# Lab10.net
KiCad netlist of a schematic drawn in Altium Designer
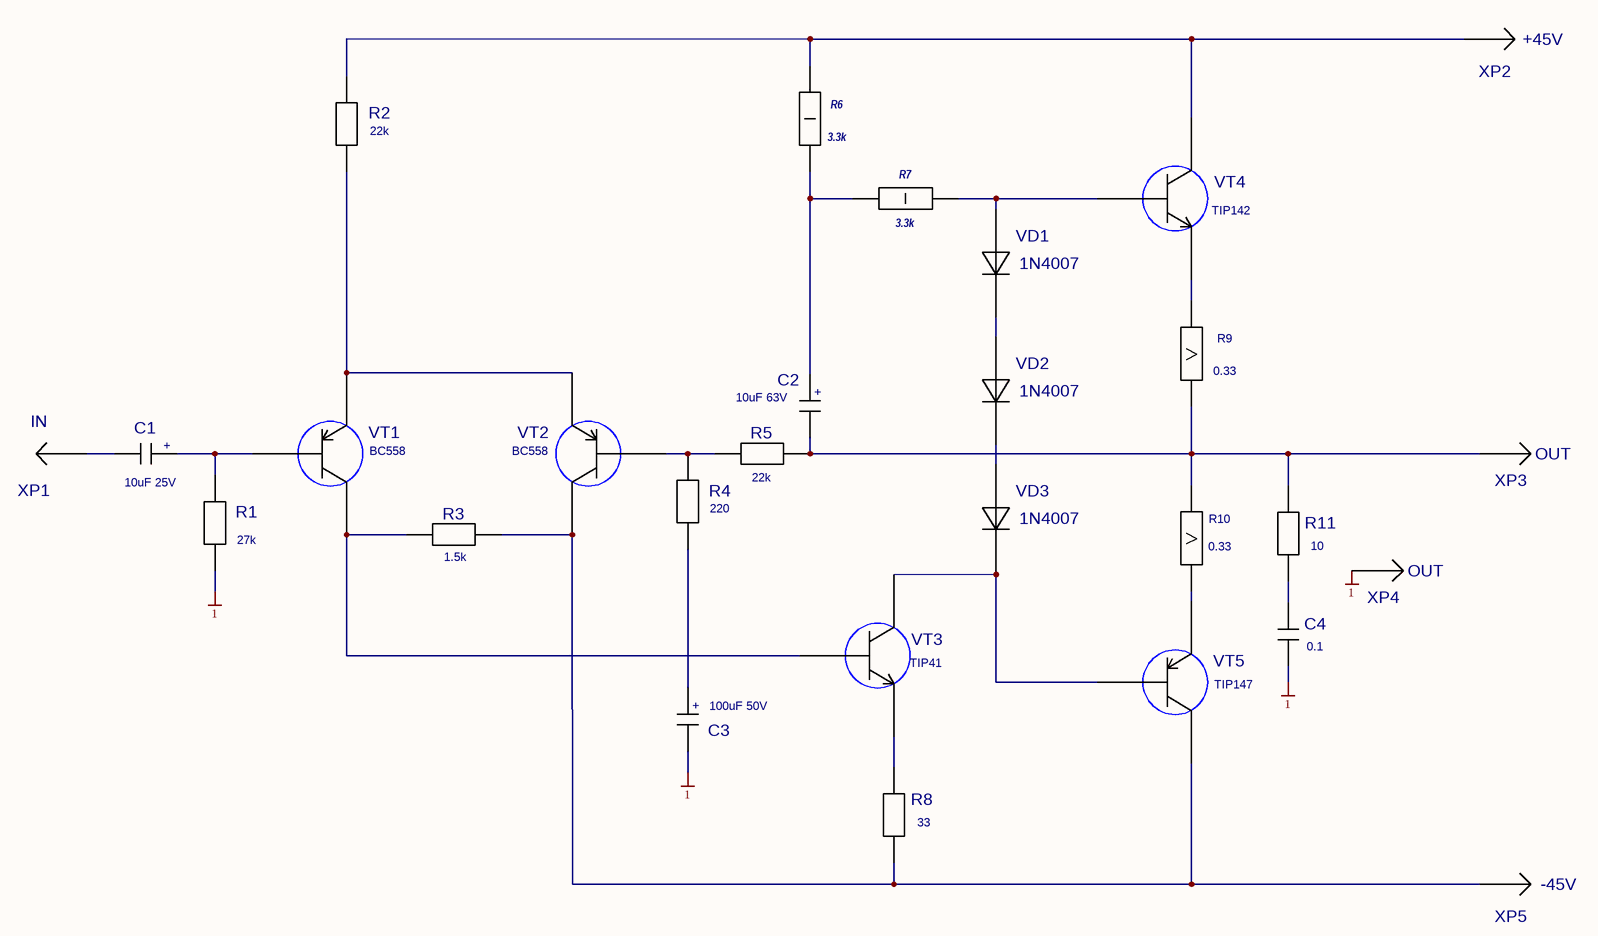
[diagram p0: Lab10.SCHDOC]

(export (version "E")
  (design (tool "Eeschema 10.0.6"))
  (components
    (comp (ref "C1")
      (value "10uF 25V")
      (footprint "CAP2")
      (description "CAP2")
      (libsource (lib "*") (part "CAP2"))
    )
    (comp (ref "C2")
      (value "10uF 63V")
      (footprint "CAP2")
      (description "CAP2")
      (libsource (lib "*") (part "CAP2"))
    )
    (comp (ref "C3")
      (value "100uF 50V")
      (footprint "CAP2")
      (description "CAP2")
      (libsource (lib "*") (part "CAP2"))
    )
    (comp (ref "C4")
      (value "0.1")
      (footprint "CAP1")
      (description "CAP1")
      (libsource (lib "*") (part "CAP1"))
    )
    (comp (ref "R1") (value "27k") (footprint "RES") (description "RES") (libsource (lib "*") (part "RES")))
    (comp (ref "R2") (value "22k") (footprint "RES") (description "RES") (libsource (lib "*") (part "RES")))
    (comp (ref "R3") (value "1.5k") (footprint "RES") (description "RES") (libsource (lib "*") (part "RES")))
    (comp (ref "R4") (value "220") (footprint "RES") (description "RES") (libsource (lib "*") (part "RES")))
    (comp (ref "R5") (value "22k") (footprint "RES") (description "RES") (libsource (lib "*") (part "RES")))
    (comp (ref "R6")
      (value "3.3k")
      (footprint "МЛТ(1)")
      (description "МЛТ(1)")
      (libsource (lib "") (part "МЛТ(1)_1"))
    )
    (comp (ref "R7")
      (value "3.3k")
      (footprint "МЛТ(1)")
      (description "МЛТ(1)")
      (libsource (lib "*") (part "МЛТ(1)"))
    )
    (comp (ref "R8") (value "33") (footprint "RES") (description "RES") (libsource (lib "*") (part "RES")))
    (comp (ref "R9")
      (value "0.33")
      (footprint "SQP5")
      (description "SQP5")
      (libsource (lib "*") (part "SQP5"))
    )
    (comp (ref "R10")
      (value "0.33")
      (footprint "SQP5")
      (description "SQP5")
      (libsource (lib "*") (part "SQP5"))
    )
    (comp (ref "R11") (value "10") (footprint "RES") (description "RES") (libsource (lib "*") (part "RES")))
    (comp (ref "VD1") (value "1N4007") (footprint "1N4007") (libsource (lib "*") (part "1N4007")))
    (comp (ref "VD2") (value "1N4007") (footprint "1N4007") (libsource (lib "*") (part "1N4007")))
    (comp (ref "VD3") (value "1N4007") (footprint "1N4007") (libsource (lib "*") (part "1N4007")))
    (comp (ref "VT1") (value "BC558") (footprint "BC558") (libsource (lib "") (part "BC558_1")))
    (comp (ref "VT2") (value "BC558") (footprint "BC558") (libsource (lib "*") (part "BC558")))
    (comp (ref "VT3") (value "TIP41") (footprint "TIP41") (libsource (lib "*") (part "TIP41")))
    (comp (ref "VT4") (value "TIP142") (footprint "TIP142") (libsource (lib "*") (part "TIP142")))
    (comp (ref "VT5") (value "TIP147") (footprint "TIP147") (libsource (lib "*") (part "TIP147")))
    (comp (ref "XP1") (value "IN") (footprint "PAD") (description "PAD") (libsource (lib "*") (part "PAD")))
    (comp (ref "XP2") (value "+45V") (footprint "PAD") (description "PAD") (libsource (lib "*") (part "PAD")))
    (comp (ref "XP3") (value "OUT") (footprint "PAD") (description "PAD") (libsource (lib "*") (part "PAD")))
    (comp (ref "XP4") (value "OUT") (footprint "PAD") (description "PAD") (libsource (lib "*") (part "PAD")))
    (comp (ref "XP5") (value "-45V") (footprint "PAD") (description "PAD") (libsource (lib "*") (part "PAD")))
  )
  (nets
    (net (code "1") (name "1") (class "Default")
      (node (ref "C3") (pin "2") (pinfunction "2_2") (pintype "passive"))
      (node (ref "C4") (pin "1") (pinfunction "1_1") (pintype "passive"))
      (node (ref "R1") (pin "1") (pinfunction "1_1") (pintype "passive"))
      (node (ref "XP4") (pin "1") (pinfunction "A1_1") (pintype "passive"))
    )
    (net (code "2") (name "Net-(C1-Pad1)") (class "Default")
      (node (ref "C1") (pin "1") (pinfunction "1_1") (pintype "passive"))
      (node (ref "R1") (pin "2") (pinfunction "2_2") (pintype "passive"))
      (node (ref "VT1") (pin "1") (pinfunction "1_1") (pintype "passive"))
    )
    (net (code "3") (name "Net-(C2-Pad1)") (class "Default")
      (node (ref "C2") (pin "1") (pinfunction "1_1") (pintype "passive"))
      (node (ref "R6") (pin "1") (pinfunction "1_1") (pintype "passive"))
      (node (ref "R7") (pin "2") (pinfunction "2_2") (pintype "passive"))
    )
    (net (code "4") (name "Net-(C3-Pad1)") (class "Default")
      (node (ref "C3") (pin "1") (pinfunction "1_1") (pintype "passive"))
      (node (ref "R4") (pin "1") (pinfunction "1_1") (pintype "passive"))
    )
    (net (code "5") (name "Net-(C4-Pad2)") (class "Default")
      (node (ref "C4") (pin "2") (pinfunction "2_2") (pintype "passive"))
      (node (ref "R11") (pin "1") (pinfunction "1_1") (pintype "passive"))
    )
    (net (code "6") (name "Net-(R2-Pad1)") (class "Default")
      (node (ref "R2") (pin "1") (pinfunction "1_1") (pintype "passive"))
      (node (ref "VT1") (pin "3") (pinfunction "3_3") (pintype "passive"))
      (node (ref "VT2") (pin "3") (pinfunction "3_3") (pintype "passive"))
    )
    (net (code "7") (name "Net-(R3-Pad2)") (class "Default")
      (node (ref "R3") (pin "2") (pinfunction "2_2") (pintype "passive"))
      (node (ref "VT1") (pin "2") (pinfunction "2_2") (pintype "passive"))
      (node (ref "VT3") (pin "1") (pinfunction "1_1") (pintype "passive"))
    )
    (net (code "8") (name "Net-(R4-Pad2)") (class "Default")
      (node (ref "R4") (pin "2") (pinfunction "2_2") (pintype "passive"))
      (node (ref "R5") (pin "2") (pinfunction "2_2") (pintype "passive"))
      (node (ref "VT2") (pin "1") (pinfunction "1_1") (pintype "passive"))
    )
    (net (code "9") (name "Net-(R8-Pad2)") (class "Default")
      (node (ref "R8") (pin "2") (pinfunction "2_2") (pintype "passive"))
      (node (ref "VT3") (pin "3") (pinfunction "3_3") (pintype "passive"))
    )
    (net (code "10") (name "Net-(R9-Pad2)") (class "Default")
      (node (ref "R9") (pin "2") (pinfunction "2_2") (pintype "passive"))
      (node (ref "VT4") (pin "3") (pinfunction "3_3") (pintype "passive"))
    )
    (net (code "11") (name "Net-(R10-Pad1)") (class "Default")
      (node (ref "R10") (pin "1") (pinfunction "1_1") (pintype "passive"))
      (node (ref "VT5") (pin "3") (pinfunction "3_3") (pintype "passive"))
    )
    (net (code "12") (name "Net-(VD1-A)") (class "Default")
      (node (ref "R7") (pin "1") (pinfunction "1_1") (pintype "passive"))
      (node (ref "VD1") (pin "2") (pinfunction "A_2") (pintype "passive"))
      (node (ref "VT4") (pin "1") (pinfunction "1_1") (pintype "passive"))
    )
    (net (code "13") (name "Net-(VD1-K)") (class "Default")
      (node (ref "VD1") (pin "1") (pinfunction "K_1") (pintype "passive"))
      (node (ref "VD2") (pin "2") (pinfunction "A_2") (pintype "passive"))
    )
    (net (code "14") (name "Net-(VD2-K)") (class "Default")
      (node (ref "VD2") (pin "1") (pinfunction "K_1") (pintype "passive"))
      (node (ref "VD3") (pin "2") (pinfunction "A_2") (pintype "passive"))
    )
    (net (code "15") (name "Net-(VD3-K)") (class "Default")
      (node (ref "VD3") (pin "1") (pinfunction "K_1") (pintype "passive"))
      (node (ref "VT3") (pin "2") (pinfunction "2_2") (pintype "passive"))
      (node (ref "VT5") (pin "1") (pinfunction "1_1") (pintype "passive"))
    )
    (net (code "16") (name "Net-(XP1-A1)") (class "Default")
      (node (ref "C1") (pin "2") (pinfunction "2_2") (pintype "passive"))
      (node (ref "XP1") (pin "1") (pinfunction "A1_1") (pintype "passive"))
    )
    (net (code "17") (name "Net-(XP2-A1)") (class "Default")
      (node (ref "R2") (pin "2") (pinfunction "2_2") (pintype "passive"))
      (node (ref "R6") (pin "2") (pinfunction "2_2") (pintype "passive"))
      (node (ref "VT4") (pin "2") (pinfunction "2_2") (pintype "passive"))
      (node (ref "XP2") (pin "1") (pinfunction "A1_1") (pintype "passive"))
    )
    (net (code "18") (name "Net-(XP3-A1)") (class "Default")
      (node (ref "C2") (pin "2") (pinfunction "2_2") (pintype "passive"))
      (node (ref "R10") (pin "2") (pinfunction "2_2") (pintype "passive"))
      (node (ref "R11") (pin "2") (pinfunction "2_2") (pintype "passive"))
      (node (ref "R5") (pin "1") (pinfunction "1_1") (pintype "passive"))
      (node (ref "R9") (pin "1") (pinfunction "1_1") (pintype "passive"))
      (node (ref "XP3") (pin "1") (pinfunction "A1_1") (pintype "passive"))
    )
    (net (code "19") (name "Net-(XP5-A1)") (class "Default")
      (node (ref "R3") (pin "1") (pinfunction "1_1") (pintype "passive"))
      (node (ref "R8") (pin "1") (pinfunction "1_1") (pintype "passive"))
      (node (ref "VT2") (pin "2") (pinfunction "2_2") (pintype "passive"))
      (node (ref "VT5") (pin "2") (pinfunction "2_2") (pintype "passive"))
      (node (ref "XP5") (pin "1") (pinfunction "A1_1") (pintype "passive"))
    )
  )
)
